# 9V_Converter.net
KiCad netlist of a schematic drawn in Altium Designer
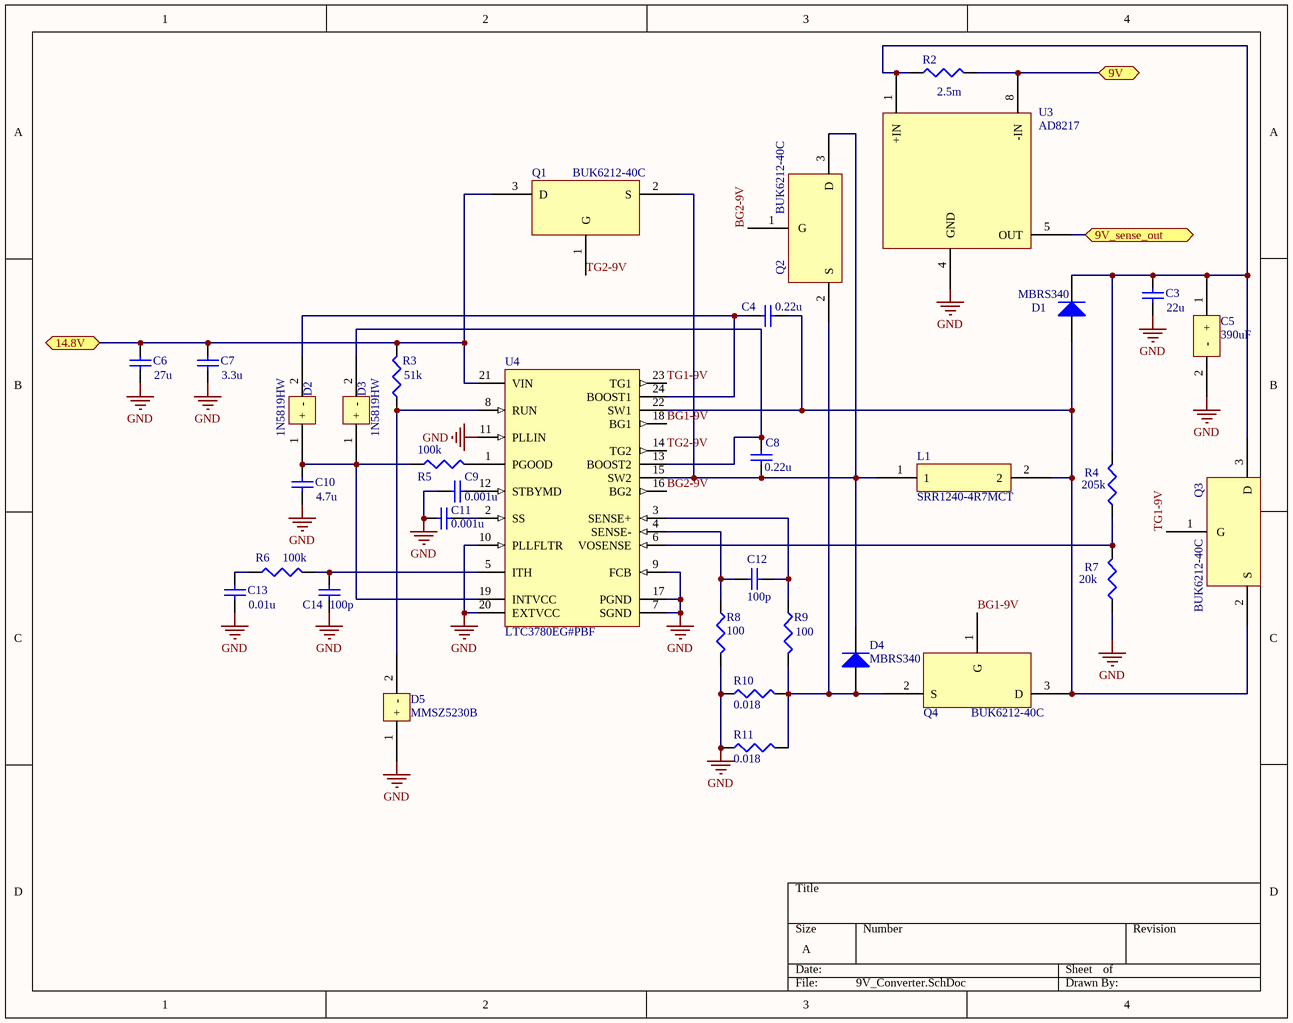
[diagram p0: 9V_Converter.SchDoc]

(export (version "E")
  (design (tool "Eeschema 10.0.6"))
  (components
    (comp (ref "C3")
      (value "22u")
      (footprint "C1206")
      (description "Capacitor (Semiconductor SIM Model)")
      (fields (field (name "Comment") "Cap Semi") (field (name "PUBLISHER") "Altium Limited"))
      (libsource (lib "Miscellaneous Devices") (part "Cap Semi"))
    )
    (comp (ref "C4")
      (value "0.22u")
      (footprint "C1206")
      (description "Capacitor (Semiconductor SIM Model)")
      (fields (field (name "Comment") "Cap Semi") (field (name "PUBLISHER") "Altium Limited"))
      (libsource (lib "Miscellaneous Devices") (part "Cap Semi"))
    )
    (comp (ref "C5")
      (value "390uF")
      (footprint "PCV1E391MCL2GS")
      (description "Aluminum Capacitor")
      (libsource (lib "Integrated_Library") (part "PCV1E391MCL2GS"))
    )
    (comp (ref "C6")
      (value "27u")
      (footprint "C1206")
      (description "Capacitor (Semiconductor SIM Model)")
      (fields (field (name "Comment") "Cap Semi") (field (name "PUBLISHER") "Altium Limited"))
      (libsource (lib "Miscellaneous Devices") (part "Cap Semi"))
    )
    (comp (ref "C7")
      (value "3.3u")
      (footprint "C1206")
      (description "Capacitor (Semiconductor SIM Model)")
      (fields (field (name "Comment") "Cap Semi") (field (name "PUBLISHER") "Altium Limited"))
      (libsource (lib "Miscellaneous Devices") (part "Cap Semi"))
    )
    (comp (ref "C8")
      (value "0.22u")
      (footprint "C1206")
      (description "Capacitor (Semiconductor SIM Model)")
      (fields (field (name "Comment") "Cap Semi") (field (name "PUBLISHER") "Altium Limited"))
      (libsource (lib "Miscellaneous Devices") (part "Cap Semi"))
    )
    (comp (ref "C9")
      (value "0.001u")
      (footprint "C1206")
      (description "Capacitor (Semiconductor SIM Model)")
      (fields (field (name "Comment") "Cap Semi") (field (name "PUBLISHER") "Altium Limited"))
      (libsource (lib "Miscellaneous Devices") (part "Cap Semi"))
    )
    (comp (ref "C10")
      (value "4.7u")
      (footprint "C1206")
      (description "Capacitor (Semiconductor SIM Model)")
      (fields (field (name "Comment") "Cap Semi") (field (name "PUBLISHER") "Altium Limited"))
      (libsource (lib "Miscellaneous Devices") (part "Cap Semi"))
    )
    (comp (ref "C11")
      (value "0.001u")
      (footprint "C1206")
      (description "Capacitor (Semiconductor SIM Model)")
      (fields (field (name "Comment") "Cap Semi") (field (name "PUBLISHER") "Altium Limited"))
      (libsource (lib "Miscellaneous Devices") (part "Cap Semi"))
    )
    (comp (ref "C12")
      (value "100p")
      (footprint "C1206")
      (description "Capacitor (Semiconductor SIM Model)")
      (fields (field (name "Comment") "Cap Semi") (field (name "PUBLISHER") "Altium Limited"))
      (libsource (lib "Miscellaneous Devices") (part "Cap Semi"))
    )
    (comp (ref "C13")
      (value "0.01u")
      (footprint "C1206")
      (description "Capacitor (Semiconductor SIM Model)")
      (fields (field (name "Comment") "Cap Semi") (field (name "PUBLISHER") "Altium Limited"))
      (libsource (lib "Miscellaneous Devices") (part "Cap Semi"))
    )
    (comp (ref "C14")
      (value "100p")
      (footprint "C1206")
      (description "Capacitor (Semiconductor SIM Model)")
      (fields (field (name "Comment") "Cap Semi") (field (name "PUBLISHER") "Altium Limited"))
      (libsource (lib "Miscellaneous Devices") (part "Cap Semi"))
    )
    (comp (ref "D1")
      (value "MBRS340")
      (footprint "SMC")
      (description "Default Diode")
      (fields (field (name "PUBLISHER") "Altium Limited"))
      (libsource (lib "Miscellaneous Devices") (part "Diode"))
    )
    (comp (ref "D2")
      (value "1N5819HW")
      (footprint "1N5819HW")
      (description "1A Schottky Barrier Rectifier")
      (libsource (lib "Integrated_Library") (part "1N5819HW"))
    )
    (comp (ref "D3")
      (value "1N5819HW")
      (footprint "1N5819HW")
      (description "1A Schottky Barrier Rectifier")
      (libsource (lib "Integrated_Library") (part "1N5819HW"))
    )
    (comp (ref "D4")
      (value "MBRS340")
      (footprint "SMC")
      (description "Default Diode")
      (fields (field (name "PUBLISHER") "Altium Limited"))
      (libsource (lib "Miscellaneous Devices") (part "Diode"))
    )
    (comp (ref "D5")
      (value "MMSZ5230B")
      (footprint "MMSZ5230B")
      (description "Zener Diode")
      (libsource (lib "Integrated_Library") (part "MMSZ5230B"))
    )
    (comp (ref "L1")
      (value "SRR1240-4R7MCT")
      (footprint "SRR1240-4R7M")
      (description "Inductor")
      (libsource (lib "Integrated_Library") (part "SRR1240-4R7MCT"))
    )
    (comp (ref "Q1")
      (value "BUK6212-40C")
      (footprint "BUK6212-40C")
      (description "N-Channel TrenchMOS Intermediate Level FET")
      (libsource (lib "") (part "BUK6212-40C_2"))
    )
    (comp (ref "Q2")
      (value "BUK6212-40C")
      (footprint "BUK6212-40C")
      (description "N-Channel TrenchMOS Intermediate Level FET")
      (libsource (lib "Integrated_Library") (part "BUK6212-40C"))
    )
    (comp (ref "Q3")
      (value "BUK6212-40C")
      (footprint "BUK6212-40C")
      (description "N-Channel TrenchMOS Intermediate Level FET")
      (libsource (lib "Integrated_Library") (part "BUK6212-40C"))
    )
    (comp (ref "Q4")
      (value "BUK6212-40C")
      (footprint "BUK6212-40C")
      (description "N-Channel TrenchMOS Intermediate Level FET")
      (libsource (lib "") (part "BUK6212-40C_1"))
    )
    (comp (ref "R2")
      (value "2.5m")
      (footprint "J1-0603")
      (description "Resistor")
      (fields (field (name "Comment") "Res3") (field (name "PUBLISHER") "Altium Limited"))
      (libsource (lib "Miscellaneous Devices") (part "Res3"))
    )
    (comp (ref "R3")
      (value "51k")
      (footprint "J1-0603")
      (description "Resistor")
      (fields (field (name "Comment") "Res3") (field (name "PUBLISHER") "Altium Limited"))
      (libsource (lib "Miscellaneous Devices") (part "Res3"))
    )
    (comp (ref "R4")
      (value "205k")
      (footprint "J1-0603")
      (description "Resistor")
      (fields (field (name "Comment") "Res3") (field (name "PUBLISHER") "Altium Limited"))
      (libsource (lib "Miscellaneous Devices") (part "Res3"))
    )
    (comp (ref "R5")
      (value "100k")
      (footprint "J1-0603")
      (description "Resistor")
      (fields (field (name "Comment") "Res3") (field (name "PUBLISHER") "Altium Limited"))
      (libsource (lib "Miscellaneous Devices") (part "Res3"))
    )
    (comp (ref "R6")
      (value "100k")
      (footprint "J1-0603")
      (description "Resistor")
      (fields (field (name "Comment") "Res3") (field (name "PUBLISHER") "Altium Limited"))
      (libsource (lib "Miscellaneous Devices") (part "Res3"))
    )
    (comp (ref "R7")
      (value "20k")
      (footprint "J1-0603")
      (description "Resistor")
      (fields (field (name "Comment") "Res3") (field (name "PUBLISHER") "Altium Limited"))
      (libsource (lib "Miscellaneous Devices") (part "Res3"))
    )
    (comp (ref "R8")
      (value "100")
      (footprint "J1-0603")
      (description "Resistor")
      (fields (field (name "Comment") "Res3") (field (name "PUBLISHER") "Altium Limited"))
      (libsource (lib "Miscellaneous Devices") (part "Res3"))
    )
    (comp (ref "R9")
      (value "100")
      (footprint "J1-0603")
      (description "Resistor")
      (fields (field (name "Comment") "Res3") (field (name "PUBLISHER") "Altium Limited"))
      (libsource (lib "Miscellaneous Devices") (part "Res3"))
    )
    (comp (ref "R10")
      (value "0.018")
      (footprint "J1-0603")
      (description "Resistor")
      (fields (field (name "Comment") "Res3") (field (name "PUBLISHER") "Altium Limited"))
      (libsource (lib "Miscellaneous Devices") (part "Res3"))
    )
    (comp (ref "R11")
      (value "0.018")
      (footprint "J1-0603")
      (description "Resistor")
      (fields (field (name "Comment") "Res3") (field (name "PUBLISHER") "Altium Limited"))
      (libsource (lib "Miscellaneous Devices") (part "Res3"))
    )
    (comp (ref "U3")
      (value "AD8217")
      (footprint "AD8217")
      (description "Current Shunt Moniter")
      (libsource (lib "Integrated_Library") (part "AD8217"))
    )
    (comp (ref "U4")
      (value "LTC3780EG#PBF")
      (footprint "LTC3780 24-Leaqd Plastic SSOP")
      (fields (field (name "MANUFACTURER") "Linear Technology"))
      (libsource (lib "Integrated_Library") (part "LTC3780EG#PBF"))
    )
  )
  (nets
    (net (code "1") (name "/9V") (class "Default")
      (node (ref "R2") (pin "2") (pinfunction "2_2") (pintype "passive"))
      (node (ref "U3") (pin "8") (pinfunction "-IN_8") (pintype "passive"))
    )
    (net (code "2") (name "/9V_sense_out") (class "Default")
      (node (ref "U3") (pin "5") (pinfunction "OUT_5") (pintype "passive"))
    )
    (net (code "3") (name "/14.8V") (class "Default")
      (node (ref "C6") (pin "2") (pinfunction "2_2") (pintype "passive"))
      (node (ref "C7") (pin "2") (pinfunction "2_2") (pintype "passive"))
      (node (ref "Q1") (pin "3") (pinfunction "D_3") (pintype "passive"))
      (node (ref "R3") (pin "2") (pinfunction "2_2") (pintype "passive"))
      (node (ref "U4") (pin "21") (pinfunction "VIN_21") (pintype "power_in"))
    )
    (net (code "4") (name "/BG1-9V") (class "Default")
      (node (ref "Q4") (pin "1") (pinfunction "G_1") (pintype "passive"))
      (node (ref "U4") (pin "18") (pinfunction "BG1_18") (pintype "output"))
    )
    (net (code "5") (name "/BG2-9V") (class "Default")
      (node (ref "Q2") (pin "1") (pinfunction "G_1") (pintype "passive"))
      (node (ref "U4") (pin "16") (pinfunction "BG2_16") (pintype "output"))
    )
    (net (code "6") (name "/TG1-9V") (class "Default")
      (node (ref "Q3") (pin "1") (pinfunction "G_1") (pintype "passive"))
      (node (ref "U4") (pin "23") (pinfunction "TG1_23") (pintype "output"))
    )
    (net (code "7") (name "/TG2-9V") (class "Default")
      (node (ref "Q1") (pin "1") (pinfunction "G_1") (pintype "passive"))
      (node (ref "U4") (pin "14") (pinfunction "TG2_14") (pintype "output"))
    )
    (net (code "8") (name "GND") (class "Default")
      (node (ref "C10") (pin "1") (pinfunction "1_1") (pintype "passive"))
      (node (ref "C11") (pin "1") (pinfunction "1_1") (pintype "passive"))
      (node (ref "C13") (pin "1") (pinfunction "1_1") (pintype "passive"))
      (node (ref "C14") (pin "1") (pinfunction "1_1") (pintype "passive"))
      (node (ref "C3") (pin "1") (pinfunction "1_1") (pintype "passive"))
      (node (ref "C5") (pin "2") (pinfunction "-_2") (pintype "passive"))
      (node (ref "C6") (pin "1") (pinfunction "1_1") (pintype "passive"))
      (node (ref "C7") (pin "1") (pinfunction "1_1") (pintype "passive"))
      (node (ref "C9") (pin "1") (pinfunction "1_1") (pintype "passive"))
      (node (ref "D5") (pin "1") (pinfunction "+_1") (pintype "passive"))
      (node (ref "R10") (pin "1") (pinfunction "1_1") (pintype "passive"))
      (node (ref "R11") (pin "1") (pinfunction "1_1") (pintype "passive"))
      (node (ref "R7") (pin "1") (pinfunction "1_1") (pintype "passive"))
      (node (ref "R8") (pin "2") (pinfunction "2_2") (pintype "passive"))
      (node (ref "U3") (pin "4") (pinfunction "GND_4") (pintype "passive"))
      (node (ref "U4") (pin "10") (pinfunction "PLLFLTR_10") (pintype "input"))
      (node (ref "U4") (pin "11") (pinfunction "PLLIN_11") (pintype "input"))
      (node (ref "U4") (pin "17") (pinfunction "PGND_17") (pintype "power_in"))
      (node (ref "U4") (pin "20") (pinfunction "EXTVCC_20") (pintype "power_in"))
      (node (ref "U4") (pin "7") (pinfunction "SGND_7") (pintype "power_in"))
      (node (ref "U4") (pin "9") (pinfunction "FCB_9") (pintype "input"))
    )
    (net (code "9") (name "Net-(C5-+)") (class "Default")
      (node (ref "C3") (pin "2") (pinfunction "2_2") (pintype "passive"))
      (node (ref "C5") (pin "1") (pinfunction "+_1") (pintype "passive"))
      (node (ref "D1") (pin "2") (pinfunction "K_2") (pintype "passive"))
      (node (ref "Q3") (pin "3") (pinfunction "D_3") (pintype "passive"))
      (node (ref "R2") (pin "1") (pinfunction "1_1") (pintype "passive"))
      (node (ref "R4") (pin "2") (pinfunction "2_2") (pintype "passive"))
      (node (ref "U3") (pin "1") (pinfunction "+IN_1") (pintype "passive"))
    )
    (net (code "10") (name "Net-(C13-Pad2)") (class "Default")
      (node (ref "C13") (pin "2") (pinfunction "2_2") (pintype "passive"))
      (node (ref "R6") (pin "1") (pinfunction "1_1") (pintype "passive"))
    )
    (net (code "11") (name "Net-(D1-A)") (class "Default")
      (node (ref "C4") (pin "1") (pinfunction "1_1") (pintype "passive"))
      (node (ref "D1") (pin "1") (pinfunction "A_1") (pintype "passive"))
      (node (ref "L1") (pin "2") (pinfunction "2_2") (pintype "passive"))
      (node (ref "Q3") (pin "2") (pinfunction "S_2") (pintype "passive"))
      (node (ref "Q4") (pin "3") (pinfunction "D_3") (pintype "passive"))
      (node (ref "U4") (pin "22") (pinfunction "SW1_22") (pintype "passive"))
    )
    (net (code "12") (name "Net-(D2-+)") (class "Default")
      (node (ref "C10") (pin "2") (pinfunction "2_2") (pintype "passive"))
      (node (ref "D2") (pin "1") (pinfunction "+_1") (pintype "passive"))
      (node (ref "D3") (pin "1") (pinfunction "+_1") (pintype "passive"))
      (node (ref "R5") (pin "1") (pinfunction "1_1") (pintype "passive"))
      (node (ref "U4") (pin "19") (pinfunction "INTVCC_19") (pintype "power_in"))
    )
    (net (code "13") (name "Net-(D2--)") (class "Default")
      (node (ref "C4") (pin "2") (pinfunction "2_2") (pintype "passive"))
      (node (ref "D2") (pin "2") (pinfunction "-_2") (pintype "passive"))
      (node (ref "U4") (pin "24") (pinfunction "BOOST1_24") (pintype "passive"))
    )
    (net (code "14") (name "Net-(D3--)") (class "Default")
      (node (ref "C8") (pin "2") (pinfunction "2_2") (pintype "passive"))
      (node (ref "D3") (pin "2") (pinfunction "-_2") (pintype "passive"))
      (node (ref "U4") (pin "13") (pinfunction "BOOST2_13") (pintype "passive"))
    )
    (net (code "15") (name "Net-(D4-A)") (class "Default")
      (node (ref "D4") (pin "1") (pinfunction "A_1") (pintype "passive"))
      (node (ref "Q2") (pin "2") (pinfunction "S_2") (pintype "passive"))
      (node (ref "Q4") (pin "2") (pinfunction "S_2") (pintype "passive"))
      (node (ref "R10") (pin "2") (pinfunction "2_2") (pintype "passive"))
      (node (ref "R11") (pin "2") (pinfunction "2_2") (pintype "passive"))
      (node (ref "R9") (pin "2") (pinfunction "2_2") (pintype "passive"))
    )
    (net (code "16") (name "Net-(D4-K)") (class "Default")
      (node (ref "C8") (pin "1") (pinfunction "1_1") (pintype "passive"))
      (node (ref "D4") (pin "2") (pinfunction "K_2") (pintype "passive"))
      (node (ref "L1") (pin "1") (pinfunction "1_1") (pintype "passive"))
      (node (ref "Q1") (pin "2") (pinfunction "S_2") (pintype "passive"))
      (node (ref "Q2") (pin "3") (pinfunction "D_3") (pintype "passive"))
      (node (ref "U4") (pin "15") (pinfunction "SW2_15") (pintype "passive"))
    )
    (net (code "17") (name "Net-(D5--)") (class "Default")
      (node (ref "D5") (pin "2") (pinfunction "-_2") (pintype "passive"))
      (node (ref "R3") (pin "1") (pinfunction "1_1") (pintype "passive"))
      (node (ref "U4") (pin "8") (pinfunction "RUN_8") (pintype "input"))
    )
    (net (code "18") (name "Net-(U4-ITH)") (class "Default")
      (node (ref "C14") (pin "2") (pinfunction "2_2") (pintype "passive"))
      (node (ref "R6") (pin "2") (pinfunction "2_2") (pintype "passive"))
      (node (ref "U4") (pin "5") (pinfunction "ITH_5") (pintype "passive"))
    )
    (net (code "19") (name "Net-(U4-PGOOD)") (class "Default")
      (node (ref "R5") (pin "2") (pinfunction "2_2") (pintype "passive"))
      (node (ref "U4") (pin "1") (pinfunction "PGOOD_1") (pintype "open_collector"))
    )
    (net (code "20") (name "Net-(U4-SENSE+)") (class "Default")
      (node (ref "C12") (pin "2") (pinfunction "2_2") (pintype "passive"))
      (node (ref "R9") (pin "1") (pinfunction "1_1") (pintype "passive"))
      (node (ref "U4") (pin "3") (pinfunction "SENSE+_3") (pintype "input"))
    )
    (net (code "21") (name "Net-(U4-SENSE-)") (class "Default")
      (node (ref "C12") (pin "1") (pinfunction "1_1") (pintype "passive"))
      (node (ref "R8") (pin "1") (pinfunction "1_1") (pintype "passive"))
      (node (ref "U4") (pin "4") (pinfunction "SENSE-_4") (pintype "input"))
    )
    (net (code "22") (name "Net-(U4-SS)") (class "Default")
      (node (ref "C11") (pin "2") (pinfunction "2_2") (pintype "passive"))
      (node (ref "U4") (pin "2") (pinfunction "SS_2") (pintype "input"))
    )
    (net (code "23") (name "Net-(U4-STBYMD)") (class "Default")
      (node (ref "C9") (pin "2") (pinfunction "2_2") (pintype "passive"))
      (node (ref "U4") (pin "12") (pinfunction "STBYMD_12") (pintype "input"))
    )
    (net (code "24") (name "Net-(U4-VOSENSE)") (class "Default")
      (node (ref "R4") (pin "1") (pinfunction "1_1") (pintype "passive"))
      (node (ref "R7") (pin "2") (pinfunction "2_2") (pintype "passive"))
      (node (ref "U4") (pin "6") (pinfunction "VOSENSE_6") (pintype "input"))
    )
  )
)
